# psu.net
KiCad netlist of a schematic drawn in EAGLE
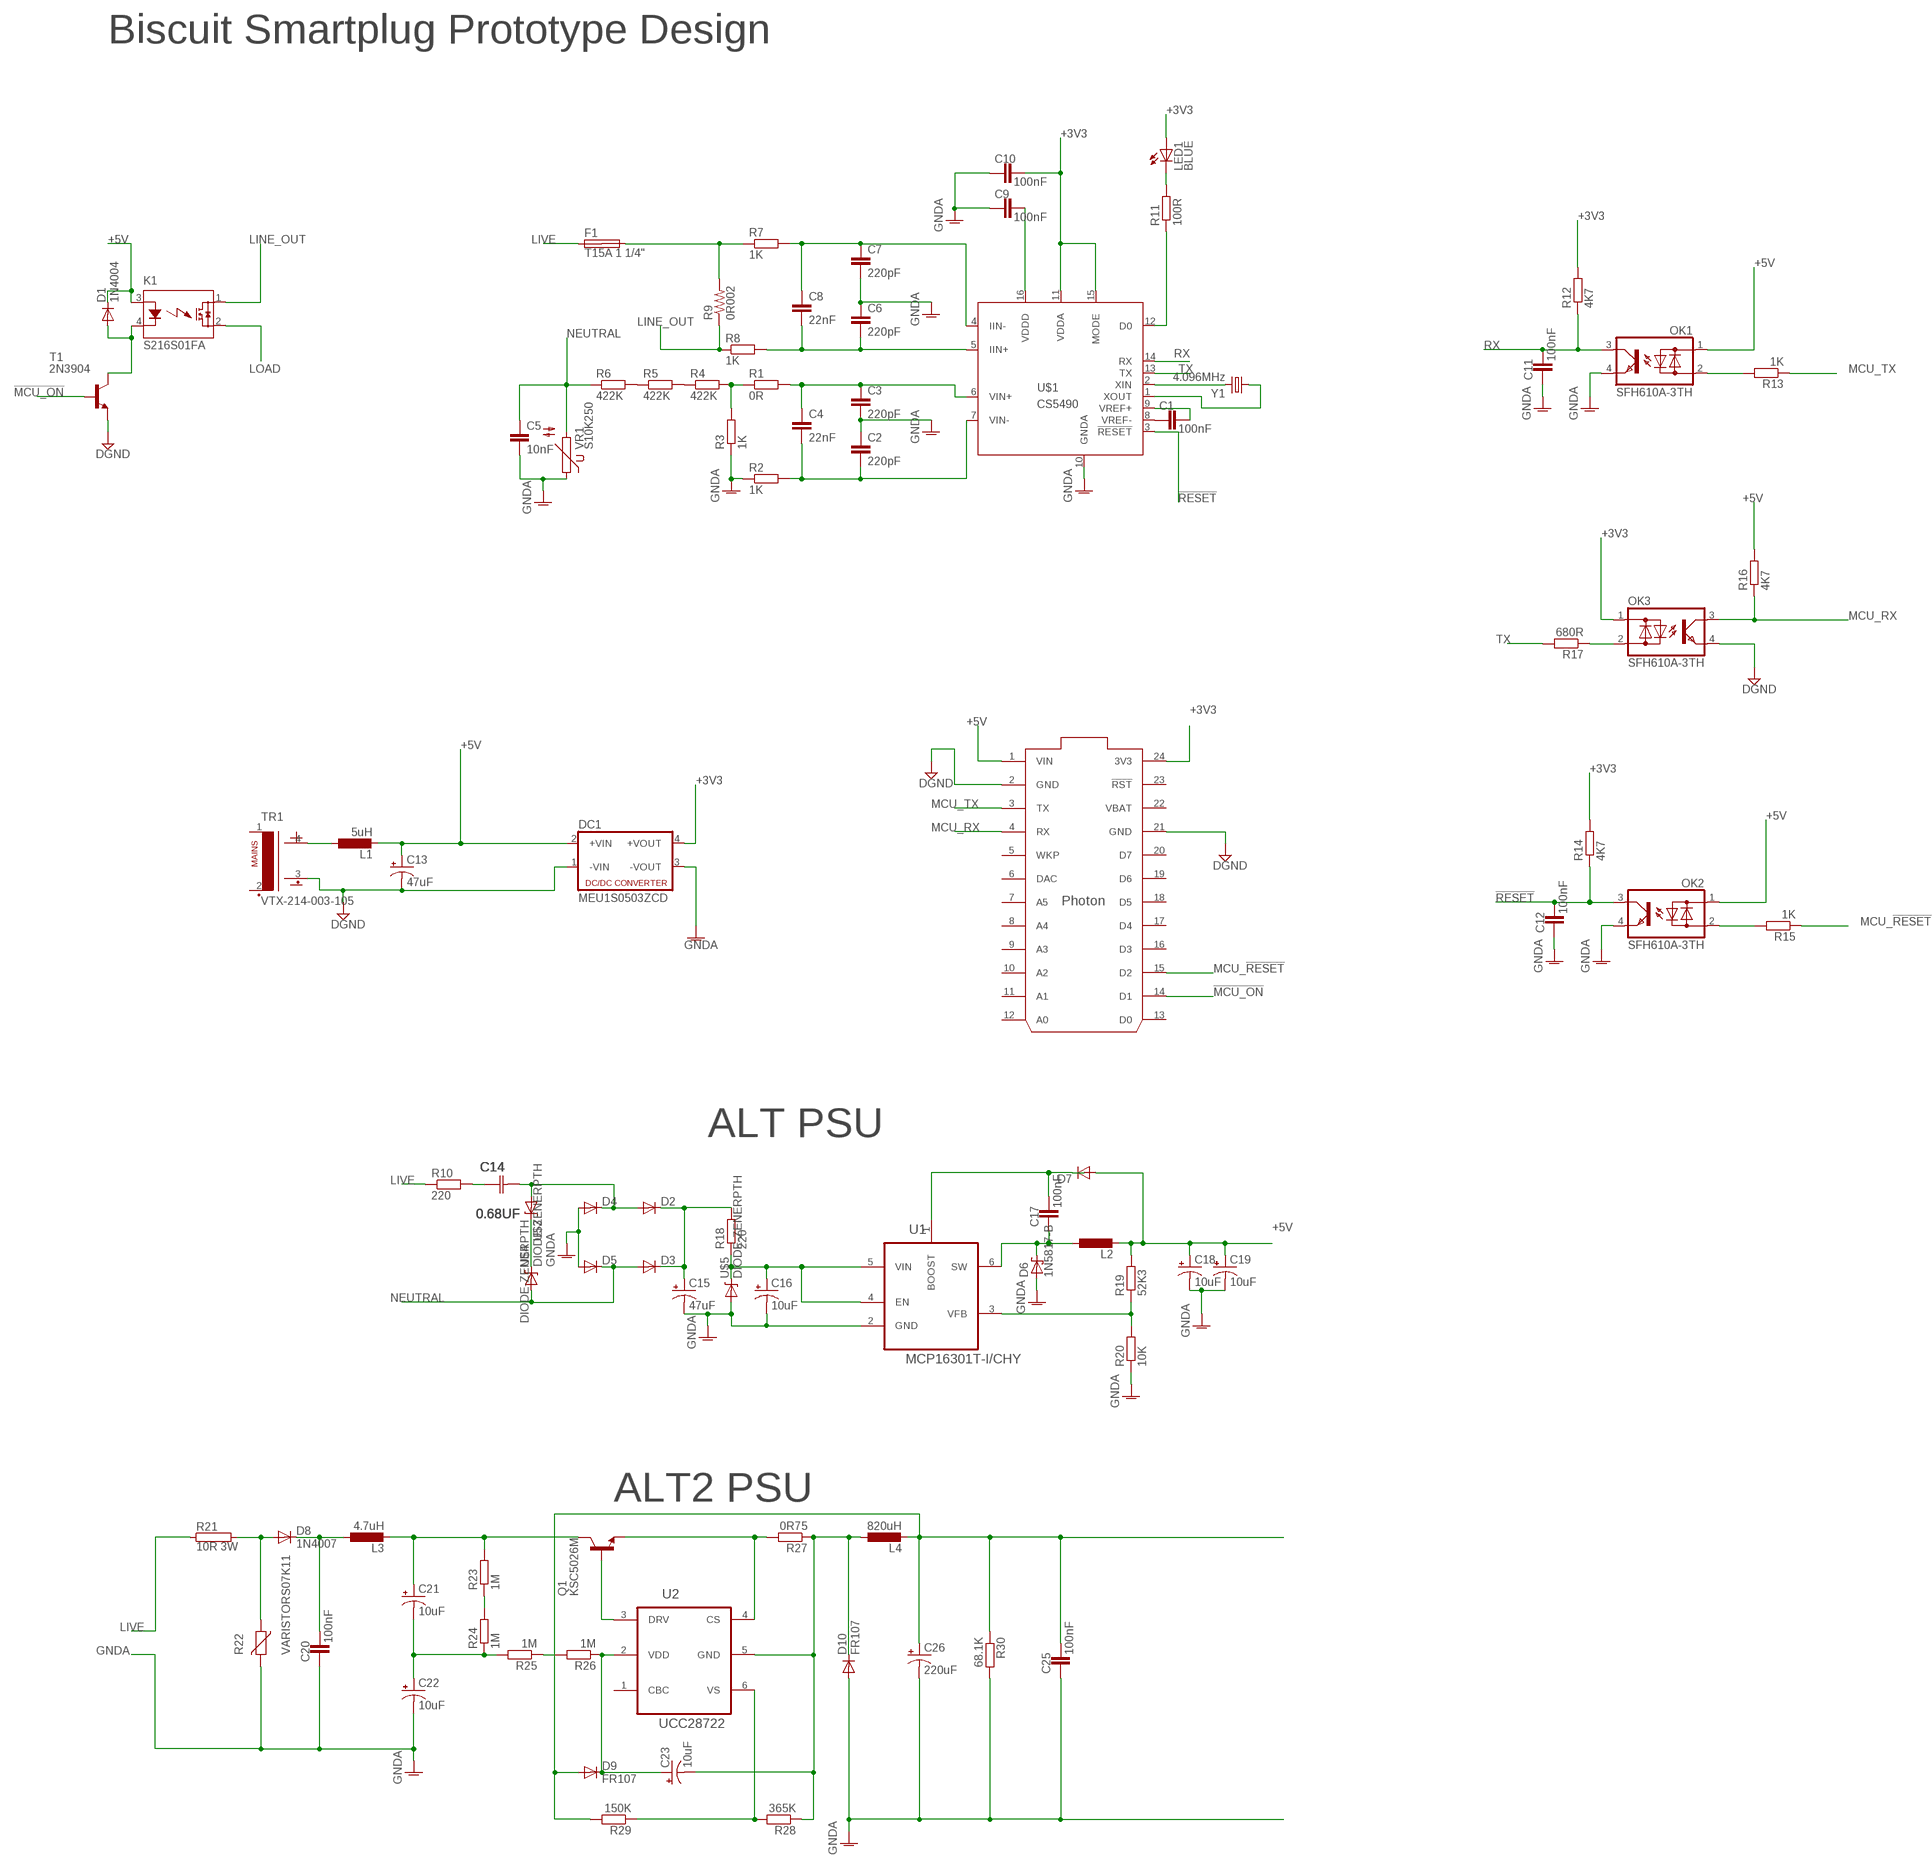
[diagram p0: schematic, sheet 1]

(export (version "E")
  (design (tool "Eeschema 10.0.6"))
  (components
    (comp (ref "C1")
      (value "100nF")
      (footprint "eagle-import:0603-CAP")
      (libsource (lib "eagle-import") (part "CAP0603-CAP"))
    )
    (comp (ref "C2")
      (value "220pF")
      (footprint "eagle-import:0603-CAP")
      (libsource (lib "eagle-import") (part "CAP0603-CAP"))
    )
    (comp (ref "C3")
      (value "220pF")
      (footprint "eagle-import:0603-CAP")
      (libsource (lib "eagle-import") (part "CAP0603-CAP"))
    )
    (comp (ref "C4")
      (value "22nF")
      (footprint "eagle-import:0603-CAP")
      (libsource (lib "eagle-import") (part "CAP0603-CAP"))
    )
    (comp (ref "C5")
      (value "10nF")
      (footprint "eagle-import:0603-CAP")
      (libsource (lib "eagle-import") (part "CAP0603-CAP"))
    )
    (comp (ref "C6")
      (value "220pF")
      (footprint "eagle-import:0603-CAP")
      (libsource (lib "eagle-import") (part "CAP0603-CAP"))
    )
    (comp (ref "C7")
      (value "220pF")
      (footprint "eagle-import:0603-CAP")
      (libsource (lib "eagle-import") (part "CAP0603-CAP"))
    )
    (comp (ref "C8")
      (value "22nF")
      (footprint "eagle-import:0603-CAP")
      (libsource (lib "eagle-import") (part "CAP0603-CAP"))
    )
    (comp (ref "C9")
      (value "100nF")
      (footprint "eagle-import:0603-CAP")
      (libsource (lib "eagle-import") (part "CAP0603-CAP"))
    )
    (comp (ref "C10")
      (value "100nF")
      (footprint "eagle-import:0603-CAP")
      (libsource (lib "eagle-import") (part "CAP0603-CAP"))
    )
    (comp (ref "C11")
      (value "100nF")
      (footprint "eagle-import:0603-CAP")
      (libsource (lib "eagle-import") (part "CAP0603-CAP"))
    )
    (comp (ref "C12")
      (value "100nF")
      (footprint "eagle-import:0603-CAP")
      (libsource (lib "eagle-import") (part "CAP0603-CAP"))
    )
    (comp (ref "C13")
      (value "47uF")
      (footprint "eagle-import:CPOL-RADIAL-100UF-25V")
      (libsource (lib "eagle-import") (part "CAP_POLPTH1"))
    )
    (comp (ref "C14")
      (value "0.68UF")
      (footprint "eagle-import:CAPM2550X1050X2000")
      (fields (field (name "MPN") "ECQU2A684KLA") (field (name "TOLERANCE") "±10%"))
      (libsource (lib "eagle-import") (part "ECQ-L25.5U2A684KLA"))
    )
    (comp (ref "C15")
      (value "47uF")
      (footprint "eagle-import:CPOL-RADIAL-100UF-25V")
      (libsource (lib "eagle-import") (part "CAP_POLPTH1"))
    )
    (comp (ref "C16")
      (value "10uF")
      (footprint "eagle-import:CPOL-RADIAL-100UF-25V")
      (libsource (lib "eagle-import") (part "CAP_POLPTH1"))
    )
    (comp (ref "C17")
      (value "100nF")
      (footprint "eagle-import:0603-CAP")
      (libsource (lib "eagle-import") (part "CAP0603-CAP"))
    )
    (comp (ref "C18")
      (value "10uF")
      (footprint "eagle-import:CPOL-RADIAL-100UF-25V")
      (libsource (lib "eagle-import") (part "CAP_POLPTH1"))
    )
    (comp (ref "C19")
      (value "10uF")
      (footprint "eagle-import:CPOL-RADIAL-100UF-25V")
      (libsource (lib "eagle-import") (part "CAP_POLPTH1"))
    )
    (comp (ref "C20")
      (value "100nF")
      (footprint "eagle-import:0603-CAP")
      (libsource (lib "eagle-import") (part "CAP0603-CAP"))
    )
    (comp (ref "C21")
      (value "10uF")
      (footprint "eagle-import:CPOL-RADIAL-100UF-25V")
      (libsource (lib "eagle-import") (part "CAP_POLPTH1"))
    )
    (comp (ref "C22")
      (value "10uF")
      (footprint "eagle-import:CPOL-RADIAL-100UF-25V")
      (libsource (lib "eagle-import") (part "CAP_POLPTH1"))
    )
    (comp (ref "C23")
      (value "10uF")
      (footprint "eagle-import:CPOL-RADIAL-100UF-25V")
      (libsource (lib "eagle-import") (part "CAP_POLPTH1"))
    )
    (comp (ref "C25")
      (value "100nF")
      (footprint "eagle-import:0603-CAP")
      (libsource (lib "eagle-import") (part "CAP0603-CAP"))
    )
    (comp (ref "C26")
      (value "220uF")
      (footprint "eagle-import:CPOL-RADIAL-100UF-25V")
      (libsource (lib "eagle-import") (part "smartplug_CAP_POLPTH1"))
    )
    (comp (ref "D1")
      (value "1N4004")
      (footprint "eagle-import:DO41-10")
      (libsource (lib "eagle-import") (part "1N4004"))
    )
    (comp (ref "D2")
      (value "DIODE1N4001")
      (footprint "eagle-import:DIODE-1N4001")
      (libsource (lib "eagle-import") (part "DIODE1N4001"))
    )
    (comp (ref "D3")
      (value "DIODE1N4001")
      (footprint "eagle-import:DIODE-1N4001")
      (libsource (lib "eagle-import") (part "DIODE1N4001"))
    )
    (comp (ref "D4")
      (value "DIODE1N4001")
      (footprint "eagle-import:DIODE-1N4001")
      (libsource (lib "eagle-import") (part "DIODE1N4001"))
    )
    (comp (ref "D5")
      (value "DIODE1N4001")
      (footprint "eagle-import:DIODE-1N4001")
      (libsource (lib "eagle-import") (part "DIODE1N4001"))
    )
    (comp (ref "D6")
      (value "1N5817-B")
      (footprint "eagle-import:DO41-7.6")
      (libsource (lib "eagle-import") (part "1N5817-B"))
    )
    (comp (ref "D7")
      (value "DIODE1N4148")
      (footprint "eagle-import:DIODE-1N4148")
      (libsource (lib "eagle-import") (part "DIODE1N4148"))
    )
    (comp (ref "D8")
      (value "1N4007")
      (footprint "eagle-import:DIODE-1N4001")
      (libsource (lib "eagle-import") (part "DIODE1N4001"))
    )
    (comp (ref "D9")
      (value "FR107")
      (footprint "eagle-import:DIODE-1N4001")
      (libsource (lib "eagle-import") (part "DIODE1N4001"))
    )
    (comp (ref "D10")
      (value "FR107")
      (footprint "eagle-import:DIODE-1N4001")
      (libsource (lib "eagle-import") (part "DIODE1N4001"))
    )
    (comp (ref "DC1")
      (value "MEU1S0503ZCD")
      (footprint "eagle-import:4-PIN-ZIF")
      (libsource (lib "eagle-import") (part "MEU1S0503ZCD"))
    )
    (comp (ref "F1")
      (value "T15A 1 1/4\"")
      (footprint "eagle-import:SH32")
      (fields (field (name "MPN") "10207101009"))
      (libsource (lib "eagle-import") (part "SH32"))
    )
    (comp (ref "K1")
      (value "S216S01FA")
      (footprint "eagle-import:S216S01F")
      (libsource (lib "eagle-import") (part "S216S01FA"))
    )
    (comp (ref "L1")
      (value "5uH")
      (footprint "eagle-import:RLB0914-4R7ML")
      (libsource (lib "eagle-import") (part "RLB0914-4R7MLA"))
    )
    (comp (ref "L2")
      (value "RLB0914-4R7MLA")
      (footprint "eagle-import:RLB0914-4R7ML")
      (libsource (lib "eagle-import") (part "RLB0914-4R7MLA"))
    )
    (comp (ref "L3")
      (value "4.7uH")
      (footprint "eagle-import:RLB0914-4R7ML")
      (libsource (lib "eagle-import") (part "RLB0914-4R7MLA"))
    )
    (comp (ref "L4")
      (value "820uH")
      (footprint "eagle-import:RLB0914-4R7ML")
      (libsource (lib "eagle-import") (part "RLB0914-4R7MLA"))
    )
    (comp (ref "LED1")
      (value "BLUE")
      (footprint "eagle-import:LED3MM")
      (libsource (lib "eagle-import") (part "LED3MM"))
    )
    (comp (ref "OK1")
      (value "SFH610A-3TH")
      (footprint "eagle-import:DIL04")
      (fields (field (name "MPN") "SFH610A-3"))
      (libsource (lib "eagle-import") (part "SFH610A-3TH"))
    )
    (comp (ref "OK2")
      (value "SFH610A-3TH")
      (footprint "eagle-import:DIL04")
      (fields (field (name "MPN") "SFH610A-3"))
      (libsource (lib "eagle-import") (part "SFH610A-3TH"))
    )
    (comp (ref "OK3")
      (value "SFH610A-3TH")
      (footprint "eagle-import:DIL04")
      (fields (field (name "MPN") "SFH610A-3"))
      (libsource (lib "eagle-import") (part "SFH610A-3TH"))
    )
    (comp (ref "Q1")
      (value "KSC5026M")
      (footprint "eagle-import:TO126")
      (libsource (lib "eagle-import") (part "KSC5026M"))
    )
    (comp (ref "R1")
      (value "0R")
      (footprint "eagle-import:0603")
      (libsource (lib "eagle-import") (part "R-EU_0603"))
    )
    (comp (ref "R2")
      (value "1K")
      (footprint "eagle-import:0603")
      (libsource (lib "eagle-import") (part "R-EU_0603"))
    )
    (comp (ref "R3")
      (value "1K")
      (footprint "eagle-import:0603")
      (libsource (lib "eagle-import") (part "R-EU_0603"))
    )
    (comp (ref "R4")
      (value "422K")
      (footprint "eagle-import:0603")
      (libsource (lib "eagle-import") (part "R-EU_0603"))
    )
    (comp (ref "R5")
      (value "422K")
      (footprint "eagle-import:0603")
      (libsource (lib "eagle-import") (part "R-EU_0603"))
    )
    (comp (ref "R6")
      (value "422K")
      (footprint "eagle-import:0603")
      (libsource (lib "eagle-import") (part "R-EU_0603"))
    )
    (comp (ref "R7")
      (value "1K")
      (footprint "eagle-import:0603")
      (libsource (lib "eagle-import") (part "R-EU_0603"))
    )
    (comp (ref "R8")
      (value "1K")
      (footprint "eagle-import:0603")
      (libsource (lib "eagle-import") (part "R-EU_0603"))
    )
    (comp (ref "R9")
      (value "0R002")
      (footprint "eagle-import:R2512")
      (libsource (lib "eagle-import") (part "RESISTOR2512"))
    )
    (comp (ref "R10")
      (value "220")
      (footprint "eagle-import:0204_7")
      (libsource (lib "eagle-import") (part "R-EU_0204/7"))
    )
    (comp (ref "R11")
      (value "100R")
      (footprint "eagle-import:0603")
      (libsource (lib "eagle-import") (part "R-EU_0603"))
    )
    (comp (ref "R12")
      (value "4K7")
      (footprint "eagle-import:0603")
      (libsource (lib "eagle-import") (part "R-EU_0603"))
    )
    (comp (ref "R13")
      (value "1K")
      (footprint "eagle-import:0603")
      (libsource (lib "eagle-import") (part "R-EU_0603"))
    )
    (comp (ref "R14")
      (value "4K7")
      (footprint "eagle-import:0603")
      (libsource (lib "eagle-import") (part "R-EU_0603"))
    )
    (comp (ref "R15")
      (value "1K")
      (footprint "eagle-import:0603")
      (libsource (lib "eagle-import") (part "R-EU_0603"))
    )
    (comp (ref "R16")
      (value "4K7")
      (footprint "eagle-import:0603")
      (libsource (lib "eagle-import") (part "R-EU_0603"))
    )
    (comp (ref "R17")
      (value "680R")
      (footprint "eagle-import:0603")
      (libsource (lib "eagle-import") (part "R-EU_0603"))
    )
    (comp (ref "R18")
      (value "220")
      (footprint "eagle-import:0204_7")
      (libsource (lib "eagle-import") (part "R-EU_0204/7"))
    )
    (comp (ref "R19")
      (value "52K3")
      (footprint "eagle-import:0204_7")
      (libsource (lib "eagle-import") (part "R-EU_0204/7"))
    )
    (comp (ref "R20")
      (value "10K")
      (footprint "eagle-import:0204_7")
      (libsource (lib "eagle-import") (part "R-EU_0204/7"))
    )
    (comp (ref "R21")
      (value "10R 3W")
      (footprint "eagle-import:AC03")
      (libsource (lib "eagle-import") (part "RAC03"))
    )
    (comp (ref "R22")
      (value "VARISTORS07K11")
      (footprint "eagle-import:S07K11")
      (libsource (lib "eagle-import") (part "VARISTORS07K11"))
    )
    (comp (ref "R23")
      (value "1M")
      (footprint "eagle-import:0204_7")
      (libsource (lib "eagle-import") (part "R-EU_0204/7"))
    )
    (comp (ref "R24")
      (value "1M")
      (footprint "eagle-import:0204_7")
      (libsource (lib "eagle-import") (part "R-EU_0204/7"))
    )
    (comp (ref "R25")
      (value "1M")
      (footprint "eagle-import:0204_7")
      (libsource (lib "eagle-import") (part "R-EU_0204/7"))
    )
    (comp (ref "R26")
      (value "1M")
      (footprint "eagle-import:0204_7")
      (libsource (lib "eagle-import") (part "R-EU_0204/7"))
    )
    (comp (ref "R27")
      (value "0R75")
      (footprint "eagle-import:0204_7")
      (libsource (lib "eagle-import") (part "R-EU_0204/7"))
    )
    (comp (ref "R28")
      (value "365K")
      (footprint "eagle-import:0204_7")
      (libsource (lib "eagle-import") (part "R-EU_0204/7"))
    )
    (comp (ref "R29")
      (value "150K")
      (footprint "eagle-import:0204_7")
      (libsource (lib "eagle-import") (part "R-EU_0204/7"))
    )
    (comp (ref "R30")
      (value "68.1K")
      (footprint "eagle-import:0204_7")
      (libsource (lib "eagle-import") (part "R-EU_0204/7"))
    )
    (comp (ref "T1")
      (value "2N3904")
      (footprint "eagle-import:TO92")
      (libsource (lib "eagle-import") (part "2N3904"))
    )
    (comp (ref "TR1")
      (value "VTX-214-003-105")
      (footprint "eagle-import:VTX-214-003-105")
      (libsource (lib "eagle-import") (part "VTX-214-003-105"))
    )
    (comp (ref "U$1")
      (value "CS5490")
      (footprint "eagle-import:SOIC16N")
      (libsource (lib "eagle-import") (part "CS5490"))
    )
    (comp (ref "U$2")
      (value "PHOTON_WITH_HEADERS")
      (footprint "eagle-import:PHOTON")
      (libsource (lib "eagle-import") (part "PHOTON_WITH_HEADERS"))
    )
    (comp (ref "U$3")
      (value "DIODE-ZENERPTH")
      (footprint "eagle-import:DIODE-ZENER")
      (libsource (lib "eagle-import") (part "DIODE-ZENERPTH"))
    )
    (comp (ref "U$4")
      (value "DIODE-ZENERPTH")
      (footprint "eagle-import:DIODE-ZENER")
      (libsource (lib "eagle-import") (part "DIODE-ZENERPTH"))
    )
    (comp (ref "U$5")
      (value "DIODE-ZENERPTH")
      (footprint "eagle-import:DIODE-ZENER")
      (libsource (lib "eagle-import") (part "DIODE-ZENERPTH"))
    )
    (comp (ref "U1")
      (value "MCP16301T-I/CHY")
      (footprint "eagle-import:SOT95P290X145-6N")
      (libsource (lib "eagle-import") (part "MCP16301T-I/CHY"))
    )
    (comp (ref "U2")
      (value "UCC28722")
      (footprint "eagle-import:SOT95P290X145-6N")
      (libsource (lib "eagle-import") (part "UCC28722"))
    )
    (comp (ref "VR1")
      (value "S10K250")
      (footprint "eagle-import:S10K250")
      (libsource (lib "eagle-import") (part "S10K250"))
    )
    (comp (ref "Y1")
      (value "4.096MHz")
      (footprint "eagle-import:CRYSTAL-SMD-10.5X4.8-2PIN")
      (libsource (lib "eagle-import") (part "CRYSTAL10.5X4.8"))
    )
  )
  (nets
    (net (code "1") (name "/+3V3") (class "Default")
      (node (ref "C10") (pin "2") (pinfunction "2_2") (pintype "passive"))
      (node (ref "DC1") (pin "4") (pinfunction "+VOUT_4") (pintype "passive"))
      (node (ref "LED1") (pin "A") (pinfunction "A_A") (pintype "passive"))
      (node (ref "OK3") (pin "1") (pinfunction "AC1_1") (pintype "passive"))
      (node (ref "R12") (pin "2") (pinfunction "2_2") (pintype "passive"))
      (node (ref "R14") (pin "2") (pinfunction "2_2") (pintype "passive"))
      (node (ref "U$1") (pin "11") (pinfunction "VDDA_11") (pintype "input"))
      (node (ref "U$1") (pin "15") (pinfunction "MODE_15") (pintype "input"))
      (node (ref "U$2") (pin "24") (pinfunction "3V3_24") (pintype "power_in"))
    )
    (net (code "2") (name "/+5V") (class "Default")
      (node (ref "C13") (pin "1") (pinfunction "+_1") (pintype "passive"))
      (node (ref "C18") (pin "1") (pinfunction "+_1") (pintype "passive"))
      (node (ref "C19") (pin "1") (pinfunction "+_1") (pintype "passive"))
      (node (ref "D1") (pin "C") (pinfunction "C_C") (pintype "passive"))
      (node (ref "D7") (pin "A") (pinfunction "A_A") (pintype "passive"))
      (node (ref "DC1") (pin "2") (pinfunction "+VIN_2") (pintype "passive"))
      (node (ref "K1") (pin "3") (pinfunction "A_3") (pintype "passive"))
      (node (ref "L1") (pin "2") (pinfunction "2_2") (pintype "passive"))
      (node (ref "L2") (pin "2") (pinfunction "2_2") (pintype "passive"))
      (node (ref "OK1") (pin "1") (pinfunction "AC1_1") (pintype "passive"))
      (node (ref "OK2") (pin "1") (pinfunction "AC1_1") (pintype "passive"))
      (node (ref "R16") (pin "2") (pinfunction "2_2") (pintype "passive"))
      (node (ref "R19") (pin "2") (pinfunction "2_2") (pintype "passive"))
      (node (ref "U$2") (pin "1") (pinfunction "VIN_1") (pintype "power_in"))
    )
    (net (code "3") (name "/LINE_OUT") (class "Default")
      (node (ref "K1") (pin "1") (pinfunction "DS1_1") (pintype "passive"))
      (node (ref "R8") (pin "1") (pinfunction "1_1") (pintype "passive"))
      (node (ref "R9") (pin "1") (pinfunction "1_1") (pintype "passive"))
    )
    (net (code "4") (name "/LIVE") (class "Default")
      (node (ref "F1") (pin "1A") (pinfunction "1A_1A") (pintype "passive"))
      (node (ref "F1") (pin "2A") (pinfunction "2A_2A") (pintype "passive"))
      (node (ref "R10") (pin "1") (pinfunction "1_1") (pintype "passive"))
      (node (ref "R21") (pin "1") (pinfunction "1_1") (pintype "passive"))
      (node (ref "R7") (pin "1") (pinfunction "1_1") (pintype "passive"))
      (node (ref "R9") (pin "2") (pinfunction "2_2") (pintype "passive"))
    )
    (net (code "5") (name "/LOAD") (class "Default")
      (node (ref "K1") (pin "2") (pinfunction "DS2_2") (pintype "passive"))
    )
    (net (code "6") (name "/MCU_RX") (class "Default")
      (node (ref "OK3") (pin "3") (pinfunction "C_3") (pintype "passive"))
      (node (ref "R16") (pin "1") (pinfunction "1_1") (pintype "passive"))
      (node (ref "U$2") (pin "4") (pinfunction "RX_4") (pintype "bidirectional"))
    )
    (net (code "7") (name "/MCU_TX") (class "Default")
      (node (ref "R13") (pin "1") (pinfunction "1_1") (pintype "passive"))
      (node (ref "U$2") (pin "3") (pinfunction "TX_3") (pintype "bidirectional"))
    )
    (net (code "8") (name "/MCU_~{RESET}") (class "Default")
      (node (ref "R15") (pin "1") (pinfunction "1_1") (pintype "passive"))
      (node (ref "U$2") (pin "15") (pinfunction "D2_15") (pintype "bidirectional"))
    )
    (net (code "9") (name "/NEUTRAL") (class "Default")
      (node (ref "C5") (pin "1") (pinfunction "1_1") (pintype "passive"))
      (node (ref "D3") (pin "A") (pinfunction "A_A") (pintype "passive"))
      (node (ref "D5") (pin "C") (pinfunction "C_C") (pintype "passive"))
      (node (ref "R6") (pin "1") (pinfunction "1_1") (pintype "passive"))
      (node (ref "U$4") (pin "P$2") (pinfunction "A_P$2") (pintype "passive"))
      (node (ref "VR1") (pin "2") (pinfunction "2_2") (pintype "passive"))
    )
    (net (code "10") (name "/RX") (class "Default")
      (node (ref "C11") (pin "2") (pinfunction "2_2") (pintype "passive"))
      (node (ref "OK1") (pin "3") (pinfunction "C_3") (pintype "passive"))
      (node (ref "R12") (pin "1") (pinfunction "1_1") (pintype "passive"))
      (node (ref "U$1") (pin "14") (pinfunction "RX_14") (pintype "input"))
    )
    (net (code "11") (name "/TX") (class "Default")
      (node (ref "R17") (pin "2") (pinfunction "2_2") (pintype "passive"))
      (node (ref "U$1") (pin "13") (pinfunction "TX_13") (pintype "output"))
    )
    (net (code "12") (name "/VBAT") (class "Default")
      (node (ref "U$2") (pin "22") (pinfunction "VBAT_22") (pintype "power_in"))
    )
    (net (code "13") (name "/~{MCU_ON}") (class "Default")
      (node (ref "T1") (pin "2") (pinfunction "B_2") (pintype "passive"))
      (node (ref "U$2") (pin "14") (pinfunction "D1_14") (pintype "bidirectional"))
    )
    (net (code "14") (name "/~{RESET}") (class "Default")
      (node (ref "C12") (pin "2") (pinfunction "2_2") (pintype "passive"))
      (node (ref "OK2") (pin "3") (pinfunction "C_3") (pintype "passive"))
      (node (ref "R14") (pin "1") (pinfunction "1_1") (pintype "passive"))
      (node (ref "U$1") (pin "3") (pinfunction "~{RESET}_3") (pintype "input"))
    )
    (net (code "15") (name "DGND") (class "Default")
      (node (ref "C13") (pin "2") (pinfunction "-_2") (pintype "passive"))
      (node (ref "DC1") (pin "1") (pinfunction "-VIN_1") (pintype "passive"))
      (node (ref "OK3") (pin "4") (pinfunction "E_4") (pintype "passive"))
      (node (ref "T1") (pin "3") (pinfunction "E_3") (pintype "passive"))
      (node (ref "TR1") (pin "3") (pinfunction "-VE_3") (pintype "passive"))
      (node (ref "U$2") (pin "2") (pinfunction "GND_2") (pintype "power_in"))
      (node (ref "U$2") (pin "21") (pinfunction "GND_21") (pintype "power_in"))
    )
    (net (code "16") (name "GNDA") (class "Default")
      (node (ref "C10") (pin "1") (pinfunction "1_1") (pintype "passive"))
      (node (ref "C11") (pin "1") (pinfunction "1_1") (pintype "passive"))
      (node (ref "C12") (pin "1") (pinfunction "1_1") (pintype "passive"))
      (node (ref "C15") (pin "2") (pinfunction "-_2") (pintype "passive"))
      (node (ref "C16") (pin "2") (pinfunction "-_2") (pintype "passive"))
      (node (ref "C18") (pin "2") (pinfunction "-_2") (pintype "passive"))
      (node (ref "C19") (pin "2") (pinfunction "-_2") (pintype "passive"))
      (node (ref "C2") (pin "1") (pinfunction "1_1") (pintype "passive"))
      (node (ref "C20") (pin "1") (pinfunction "1_1") (pintype "passive"))
      (node (ref "C22") (pin "2") (pinfunction "-_2") (pintype "passive"))
      (node (ref "C25") (pin "1") (pinfunction "1_1") (pintype "passive"))
      (node (ref "C26") (pin "2") (pinfunction "-_2") (pintype "passive"))
      (node (ref "C3") (pin "2") (pinfunction "2_2") (pintype "passive"))
      (node (ref "C5") (pin "2") (pinfunction "2_2") (pintype "passive"))
      (node (ref "C6") (pin "1") (pinfunction "1_1") (pintype "passive"))
      (node (ref "C7") (pin "2") (pinfunction "2_2") (pintype "passive"))
      (node (ref "C9") (pin "1") (pinfunction "1_1") (pintype "passive"))
      (node (ref "D10") (pin "A") (pinfunction "A_A") (pintype "passive"))
      (node (ref "D4") (pin "A") (pinfunction "A_A") (pintype "passive"))
      (node (ref "D5") (pin "A") (pinfunction "A_A") (pintype "passive"))
      (node (ref "D6") (pin "A") (pinfunction "A_A") (pintype "passive"))
      (node (ref "DC1") (pin "3") (pinfunction "-VOUT_3") (pintype "passive"))
      (node (ref "OK1") (pin "4") (pinfunction "E_4") (pintype "passive"))
      (node (ref "OK2") (pin "4") (pinfunction "E_4") (pintype "passive"))
      (node (ref "R2") (pin "1") (pinfunction "1_1") (pintype "passive"))
      (node (ref "R20") (pin "1") (pinfunction "1_1") (pintype "passive"))
      (node (ref "R22") (pin "2") (pinfunction "2_2") (pintype "passive"))
      (node (ref "R3") (pin "1") (pinfunction "1_1") (pintype "passive"))
      (node (ref "R30") (pin "2") (pinfunction "2_2") (pintype "passive"))
      (node (ref "U$1") (pin "10") (pinfunction "GNDA_10") (pintype "power_in"))
      (node (ref "U$5") (pin "P$2") (pinfunction "A_P$2") (pintype "passive"))
      (node (ref "U1") (pin "2") (pinfunction "GND_2") (pintype "passive"))
      (node (ref "VR1") (pin "1") (pinfunction "1_1") (pintype "passive"))
    )
    (net (code "17") (name "Net-(C14-Pad1)") (class "Default")
      (node (ref "C14") (pin "1") (pinfunction "1_1") (pintype "passive"))
      (node (ref "R10") (pin "2") (pinfunction "2_2") (pintype "passive"))
    )
    (net (code "18") (name "Net-(C15-+)") (class "Default")
      (node (ref "C15") (pin "1") (pinfunction "+_1") (pintype "passive"))
      (node (ref "D2") (pin "C") (pinfunction "C_C") (pintype "passive"))
      (node (ref "D3") (pin "C") (pinfunction "C_C") (pintype "passive"))
      (node (ref "R18") (pin "2") (pinfunction "2_2") (pintype "passive"))
    )
    (net (code "19") (name "Net-(C16-+)") (class "Default")
      (node (ref "C16") (pin "1") (pinfunction "+_1") (pintype "passive"))
      (node (ref "R18") (pin "1") (pinfunction "1_1") (pintype "passive"))
      (node (ref "U$5") (pin "P$1") (pinfunction "C_P$1") (pintype "passive"))
      (node (ref "U1") (pin "4") (pinfunction "EN_4") (pintype "input"))
      (node (ref "U1") (pin "5") (pinfunction "VIN_5") (pintype "input"))
    )
    (net (code "20") (name "Net-(C20-Pad2)") (class "Default")
      (node (ref "C20") (pin "2") (pinfunction "2_2") (pintype "passive"))
      (node (ref "D8") (pin "C") (pinfunction "C_C") (pintype "passive"))
      (node (ref "L3") (pin "1") (pinfunction "1_1") (pintype "passive"))
    )
    (net (code "21") (name "Net-(C21-+)") (class "Default")
      (node (ref "C21") (pin "1") (pinfunction "+_1") (pintype "passive"))
      (node (ref "L3") (pin "2") (pinfunction "2_2") (pintype "passive"))
      (node (ref "Q1") (pin "2") (pinfunction "C_2") (pintype "passive"))
      (node (ref "R23") (pin "2") (pinfunction "2_2") (pintype "passive"))
    )
    (net (code "22") (name "Net-(C21--)") (class "Default")
      (node (ref "C21") (pin "2") (pinfunction "-_2") (pintype "passive"))
      (node (ref "C22") (pin "1") (pinfunction "+_1") (pintype "passive"))
      (node (ref "R24") (pin "1") (pinfunction "1_1") (pintype "passive"))
      (node (ref "R25") (pin "2") (pinfunction "2_2") (pintype "passive"))
    )
    (net (code "23") (name "Net-(C23-+)") (class "Default")
      (node (ref "C23") (pin "1") (pinfunction "+_1") (pintype "passive"))
      (node (ref "D9") (pin "C") (pinfunction "C_C") (pintype "passive"))
      (node (ref "R26") (pin "1") (pinfunction "1_1") (pintype "passive"))
      (node (ref "U2") (pin "2") (pinfunction "VDD_2") (pintype "power_in"))
    )
    (net (code "24") (name "Net-(C23--)") (class "Default")
      (node (ref "C23") (pin "2") (pinfunction "-_2") (pintype "passive"))
      (node (ref "D10") (pin "C") (pinfunction "C_C") (pintype "passive"))
      (node (ref "L4") (pin "1") (pinfunction "1_1") (pintype "passive"))
      (node (ref "R27") (pin "1") (pinfunction "1_1") (pintype "passive"))
      (node (ref "R28") (pin "1") (pinfunction "1_1") (pintype "passive"))
      (node (ref "U2") (pin "5") (pinfunction "GND_5") (pintype "passive"))
    )
    (net (code "25") (name "Net-(C26-+)") (class "Default")
      (node (ref "C25") (pin "2") (pinfunction "2_2") (pintype "passive"))
      (node (ref "C26") (pin "1") (pinfunction "+_1") (pintype "passive"))
      (node (ref "D9") (pin "A") (pinfunction "A_A") (pintype "passive"))
      (node (ref "L4") (pin "2") (pinfunction "2_2") (pintype "passive"))
      (node (ref "R29") (pin "2") (pinfunction "2_2") (pintype "passive"))
      (node (ref "R30") (pin "1") (pinfunction "1_1") (pintype "passive"))
    )
    (net (code "26") (name "Net-(D8-PadA)") (class "Default")
      (node (ref "D8") (pin "A") (pinfunction "A_A") (pintype "passive"))
      (node (ref "R21") (pin "2") (pinfunction "2_2") (pintype "passive"))
      (node (ref "R22") (pin "1") (pinfunction "1_1") (pintype "passive"))
    )
    (net (code "27") (name "Net-(K1-K)") (class "Default")
      (node (ref "D1") (pin "A") (pinfunction "A_A") (pintype "passive"))
      (node (ref "K1") (pin "4") (pinfunction "K_4") (pintype "passive"))
      (node (ref "T1") (pin "1") (pinfunction "C_1") (pintype "passive"))
    )
    (net (code "28") (name "Net-(LED1-C)") (class "Default")
      (node (ref "LED1") (pin "K") (pinfunction "C_K") (pintype "passive"))
      (node (ref "R11") (pin "2") (pinfunction "2_2") (pintype "passive"))
    )
    (net (code "29") (name "Net-(OK1-AC2)") (class "Default")
      (node (ref "OK1") (pin "2") (pinfunction "AC2_2") (pintype "passive"))
      (node (ref "R13") (pin "2") (pinfunction "2_2") (pintype "passive"))
    )
    (net (code "30") (name "Net-(OK2-AC2)") (class "Default")
      (node (ref "OK2") (pin "2") (pinfunction "AC2_2") (pintype "passive"))
      (node (ref "R15") (pin "2") (pinfunction "2_2") (pintype "passive"))
    )
    (net (code "31") (name "Net-(OK3-AC2)") (class "Default")
      (node (ref "OK3") (pin "2") (pinfunction "AC2_2") (pintype "passive"))
      (node (ref "R17") (pin "1") (pinfunction "1_1") (pintype "passive"))
    )
    (net (code "32") (name "Net-(Q1-B)") (class "Default")
      (node (ref "Q1") (pin "3") (pinfunction "B_3") (pintype "passive"))
      (node (ref "U2") (pin "3") (pinfunction "DRV_3") (pintype "output"))
    )
    (net (code "33") (name "Net-(Q1-E)") (class "Default")
      (node (ref "Q1") (pin "1") (pinfunction "E_1") (pintype "passive"))
      (node (ref "R27") (pin "2") (pinfunction "2_2") (pintype "passive"))
      (node (ref "U2") (pin "4") (pinfunction "CS_4") (pintype "input"))
    )
    (net (code "34") (name "Net-(R1-Pad1)") (class "Default")
      (node (ref "R1") (pin "1") (pinfunction "1_1") (pintype "passive"))
      (node (ref "R3") (pin "2") (pinfunction "2_2") (pintype "passive"))
      (node (ref "R4") (pin "2") (pinfunction "2_2") (pintype "passive"))
    )
    (net (code "35") (name "Net-(R4-Pad1)") (class "Default")
      (node (ref "R4") (pin "1") (pinfunction "1_1") (pintype "passive"))
      (node (ref "R5") (pin "2") (pinfunction "2_2") (pintype "passive"))
    )
    (net (code "36") (name "Net-(R5-Pad1)") (class "Default")
      (node (ref "R5") (pin "1") (pinfunction "1_1") (pintype "passive"))
      (node (ref "R6") (pin "2") (pinfunction "2_2") (pintype "passive"))
    )
    (net (code "37") (name "Net-(R23-Pad1)") (class "Default")
      (node (ref "R23") (pin "1") (pinfunction "1_1") (pintype "passive"))
      (node (ref "R24") (pin "2") (pinfunction "2_2") (pintype "passive"))
    )
    (net (code "38") (name "Net-(R25-Pad1)") (class "Default")
      (node (ref "R25") (pin "1") (pinfunction "1_1") (pintype "passive"))
      (node (ref "R26") (pin "2") (pinfunction "2_2") (pintype "passive"))
    )
    (net (code "39") (name "Net-(TR1-+VE)") (class "Default")
      (node (ref "L1") (pin "1") (pinfunction "1_1") (pintype "passive"))
      (node (ref "TR1") (pin "4") (pinfunction "+VE_4") (pintype "passive"))
    )
    (net (code "40") (name "Net-(U$1-D0)") (class "Default")
      (node (ref "R11") (pin "1") (pinfunction "1_1") (pintype "passive"))
      (node (ref "U$1") (pin "12") (pinfunction "D0_12") (pintype "output"))
    )
    (net (code "41") (name "Net-(U$1-IIN+)") (class "Default")
      (node (ref "C6") (pin "2") (pinfunction "2_2") (pintype "passive"))
      (node (ref "C8") (pin "2") (pinfunction "2_2") (pintype "passive"))
      (node (ref "R8") (pin "2") (pinfunction "2_2") (pintype "passive"))
      (node (ref "U$1") (pin "5") (pinfunction "IIN+_5") (pintype "input"))
    )
    (net (code "42") (name "Net-(U$1-IIN-)") (class "Default")
      (node (ref "C7") (pin "1") (pinfunction "1_1") (pintype "passive"))
      (node (ref "C8") (pin "1") (pinfunction "1_1") (pintype "passive"))
      (node (ref "R7") (pin "2") (pinfunction "2_2") (pintype "passive"))
      (node (ref "U$1") (pin "4") (pinfunction "IIN-_4") (pintype "input"))
    )
    (net (code "43") (name "Net-(U$1-VDDD)") (class "Default")
      (node (ref "C9") (pin "2") (pinfunction "2_2") (pintype "passive"))
      (node (ref "U$1") (pin "16") (pinfunction "VDDD_16") (pintype "power_in"))
    )
    (net (code "44") (name "Net-(U$1-VIN+)") (class "Default")
      (node (ref "C3") (pin "1") (pinfunction "1_1") (pintype "passive"))
      (node (ref "C4") (pin "1") (pinfunction "1_1") (pintype "passive"))
      (node (ref "R1") (pin "2") (pinfunction "2_2") (pintype "passive"))
      (node (ref "U$1") (pin "6") (pinfunction "VIN+_6") (pintype "input"))
    )
    (net (code "45") (name "Net-(U$1-VIN-)") (class "Default")
      (node (ref "C2") (pin "2") (pinfunction "2_2") (pintype "passive"))
      (node (ref "C4") (pin "2") (pinfunction "2_2") (pintype "passive"))
      (node (ref "R2") (pin "2") (pinfunction "2_2") (pintype "passive"))
      (node (ref "U$1") (pin "7") (pinfunction "VIN-_7") (pintype "input"))
    )
    (net (code "46") (name "Net-(U$1-VREF+)") (class "Default")
      (node (ref "C1") (pin "2") (pinfunction "2_2") (pintype "passive"))
      (node (ref "U$1") (pin "9") (pinfunction "VREF+_9") (pintype "output"))
    )
    (net (code "47") (name "Net-(U$1-VREF-)") (class "Default")
      (node (ref "C1") (pin "1") (pinfunction "1_1") (pintype "passive"))
      (node (ref "U$1") (pin "8") (pinfunction "VREF-_8") (pintype "input"))
    )
    (net (code "48") (name "Net-(U$1-XIN)") (class "Default")
      (node (ref "U$1") (pin "2") (pinfunction "XIN_2") (pintype "input"))
      (node (ref "Y1") (pin "P$2") (pinfunction "2_P$2") (pintype "passive"))
    )
    (net (code "49") (name "Net-(U$1-XOUT)") (class "Default")
      (node (ref "U$1") (pin "1") (pinfunction "XOUT_1") (pintype "output"))
      (node (ref "Y1") (pin "P$1") (pinfunction "1_P$1") (pintype "passive"))
    )
    (net (code "50") (name "Net-(U$3-A)") (class "Default")
      (node (ref "C14") (pin "2") (pinfunction "2_2") (pintype "passive"))
      (node (ref "D2") (pin "A") (pinfunction "A_A") (pintype "passive"))
      (node (ref "D4") (pin "C") (pinfunction "C_C") (pintype "passive"))
      (node (ref "U$3") (pin "P$2") (pinfunction "A_P$2") (pintype "passive"))
    )
    (net (code "51") (name "Net-(U$3-C)") (class "Default")
      (node (ref "U$3") (pin "P$1") (pinfunction "C_P$1") (pintype "passive"))
      (node (ref "U$4") (pin "P$1") (pinfunction "C_P$1") (pintype "passive"))
    )
    (net (code "52") (name "Net-(U1-BOOST)") (class "Default")
      (node (ref "C17") (pin "2") (pinfunction "2_2") (pintype "passive"))
      (node (ref "D7") (pin "C") (pinfunction "C_C") (pintype "passive"))
      (node (ref "U1") (pin "1") (pinfunction "BOOST_1") (pintype "passive"))
    )
    (net (code "53") (name "Net-(U1-SW)") (class "Default")
      (node (ref "C17") (pin "1") (pinfunction "1_1") (pintype "passive"))
      (node (ref "D6") (pin "C") (pinfunction "C_C") (pintype "passive"))
      (node (ref "L2") (pin "1") (pinfunction "1_1") (pintype "passive"))
      (node (ref "U1") (pin "6") (pinfunction "SW_6") (pintype "output"))
    )
    (net (code "54") (name "Net-(U1-VFB)") (class "Default")
      (node (ref "R19") (pin "1") (pinfunction "1_1") (pintype "passive"))
      (node (ref "R20") (pin "2") (pinfunction "2_2") (pintype "passive"))
      (node (ref "U1") (pin "3") (pinfunction "VFB_3") (pintype "output"))
    )
    (net (code "55") (name "Net-(U2-VS)") (class "Default")
      (node (ref "R28") (pin "2") (pinfunction "2_2") (pintype "passive"))
      (node (ref "R29") (pin "1") (pinfunction "1_1") (pintype "passive"))
      (node (ref "U2") (pin "6") (pinfunction "VS_6") (pintype "input"))
    )
    (net (code "56") (name "unconnected-(F1-Pad1B)") (class "Default")
      (node (ref "F1") (pin "1B") (pinfunction "1B_1B") (pintype "passive"))
    )
    (net (code "57") (name "unconnected-(F1-Pad2B)") (class "Default")
      (node (ref "F1") (pin "2B") (pinfunction "2B_2B") (pintype "passive"))
    )
    (net (code "58") (name "unconnected-(TR1-L-Pad1)") (class "Default")
      (node (ref "TR1") (pin "1") (pinfunction "L_1") (pintype "passive"))
    )
    (net (code "59") (name "unconnected-(TR1-N-Pad2)") (class "Default")
      (node (ref "TR1") (pin "2") (pinfunction "N_2") (pintype "passive"))
    )
    (net (code "60") (name "unconnected-(U$2-A0-Pad12)") (class "Default")
      (node (ref "U$2") (pin "12") (pinfunction "A0_12") (pintype "bidirectional"))
    )
    (net (code "61") (name "unconnected-(U$2-A1-Pad11)") (class "Default")
      (node (ref "U$2") (pin "11") (pinfunction "A1_11") (pintype "bidirectional"))
    )
    (net (code "62") (name "unconnected-(U$2-A2-Pad10)") (class "Default")
      (node (ref "U$2") (pin "10") (pinfunction "A2_10") (pintype "bidirectional"))
    )
    (net (code "63") (name "unconnected-(U$2-A3-Pad9)") (class "Default")
      (node (ref "U$2") (pin "9") (pinfunction "A3_9") (pintype "bidirectional"))
    )
    (net (code "64") (name "unconnected-(U$2-A4-Pad8)") (class "Default")
      (node (ref "U$2") (pin "8") (pinfunction "A4_8") (pintype "bidirectional"))
    )
    (net (code "65") (name "unconnected-(U$2-A5-Pad7)") (class "Default")
      (node (ref "U$2") (pin "7") (pinfunction "A5_7") (pintype "bidirectional"))
    )
    (net (code "66") (name "unconnected-(U$2-D0-Pad13)") (class "Default")
      (node (ref "U$2") (pin "13") (pinfunction "D0_13") (pintype "bidirectional"))
    )
    (net (code "67") (name "unconnected-(U$2-D3-Pad16)") (class "Default")
      (node (ref "U$2") (pin "16") (pinfunction "D3_16") (pintype "bidirectional"))
    )
    (net (code "68") (name "unconnected-(U$2-D4-Pad17)") (class "Default")
      (node (ref "U$2") (pin "17") (pinfunction "D4_17") (pintype "bidirectional"))
    )
    (net (code "69") (name "unconnected-(U$2-D5-Pad18)") (class "Default")
      (node (ref "U$2") (pin "18") (pinfunction "D5_18") (pintype "bidirectional"))
    )
    (net (code "70") (name "unconnected-(U$2-D6-Pad19)") (class "Default")
      (node (ref "U$2") (pin "19") (pinfunction "D6_19") (pintype "bidirectional"))
    )
    (net (code "71") (name "unconnected-(U$2-D7-Pad20)") (class "Default")
      (node (ref "U$2") (pin "20") (pinfunction "D7_20") (pintype "bidirectional"))
    )
    (net (code "72") (name "unconnected-(U$2-DAC-Pad6)") (class "Default")
      (node (ref "U$2") (pin "6") (pinfunction "DAC_6") (pintype "bidirectional"))
    )
    (net (code "73") (name "unconnected-(U$2-WKP-Pad5)") (class "Default")
      (node (ref "U$2") (pin "5") (pinfunction "WKP_5") (pintype "bidirectional"))
    )
    (net (code "74") (name "unconnected-(U$2-~{RST}-Pad23)") (class "Default")
      (node (ref "U$2") (pin "23") (pinfunction "~{RST}_23") (pintype "bidirectional"))
    )
    (net (code "75") (name "unconnected-(U2-CBC-Pad1)") (class "Default")
      (node (ref "U2") (pin "1") (pinfunction "CBC_1") (pintype "passive"))
    )
  )
)
